# Motor.net
KiCad netlist of a schematic drawn in Altium Designer
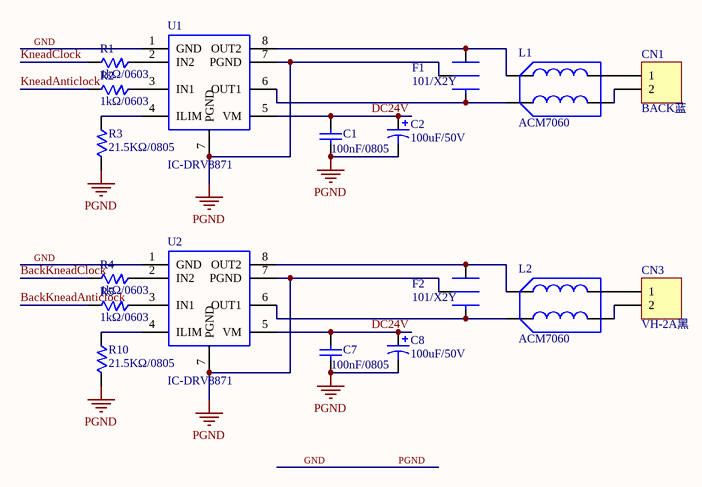
[diagram p0: Motor.SchDoc]

(export (version "E")
  (design (tool "Eeschema 10.0.6"))
  (components
    (comp (ref "C1") (value "100nF/0805") (footprint "0805C") (libsource (lib "荣泰料号库") (part "C0805/104M")))
    (comp (ref "C2")
      (value "100uF/50V")
      (footprint "RB.15/.35")
      (libsource (lib "荣泰料号库") (part "CD/100uF/50V"))
    )
    (comp (ref "C7") (value "100nF/0805") (footprint "0805C") (libsource (lib "荣泰料号库") (part "C0805/104M")))
    (comp (ref "C8")
      (value "100uF/50V")
      (footprint "RB.15/.35")
      (libsource (lib "荣泰料号库") (part "CD/100uF/50V"))
    )
    (comp (ref "CN1")
      (value "BACK蓝")
      (footprint "CON-VH-2P")
      (libsource (lib "荣泰料号库") (part "CON-VH-2A(蓝色)"))
    )
    (comp (ref "CN3")
      (value "VH-2A黑")
      (footprint "CON-VH-2P")
      (libsource (lib "荣泰料号库") (part "CON-VH-2A(黑色)"))
    )
    (comp (ref "F1") (value "101/X2Y") (footprint "X2Y") (libsource (lib "荣泰料号库") (part "CX2Y/101")))
    (comp (ref "F2") (value "101/X2Y") (footprint "X2Y") (libsource (lib "荣泰料号库") (part "CX2Y/101")))
    (comp (ref "L1") (value "ACM7060") (footprint "TLDCM7161") (libsource (lib "荣泰料号库") (part "L/ACM7060")))
    (comp (ref "L2") (value "ACM7060") (footprint "TLDCM7161") (libsource (lib "荣泰料号库") (part "L/ACM7060")))
    (comp (ref "R1") (value "1kΩ/0603") (footprint "0603") (libsource (lib "荣泰料号库") (part "R0603/1kΩ")))
    (comp (ref "R2") (value "1kΩ/0603") (footprint "0603") (libsource (lib "荣泰料号库") (part "R0603/1kΩ")))
    (comp (ref "R3")
      (value "21.5KΩ/0805")
      (footprint "0603")
      (libsource (lib "荣泰料号库") (part "R0603/21.5KΩ 1%"))
    )
    (comp (ref "R4") (value "1kΩ/0603") (footprint "0603") (libsource (lib "荣泰料号库") (part "R0603/1kΩ")))
    (comp (ref "R5") (value "1kΩ/0603") (footprint "0603") (libsource (lib "荣泰料号库") (part "R0603/1kΩ")))
    (comp (ref "R10")
      (value "21.5KΩ/0805")
      (footprint "0603")
      (libsource (lib "荣泰料号库") (part "R0603/21.5KΩ 1%"))
    )
    (comp (ref "U1") (value "IC-DRV8871") (footprint "DRV8871") (libsource (lib "荣泰料号库") (part "IC-DRV8871")))
    (comp (ref "U2") (value "IC-DRV8871") (footprint "DRV8871") (libsource (lib "荣泰料号库") (part "IC-DRV8871")))
  )
  (nets
    (net (code "1") (name "/BackKneadAnticlock") (class "Default")
      (node (ref "R5") (pin "1") (pinfunction "1_1") (pintype "passive"))
    )
    (net (code "2") (name "/BackKneadClock") (class "Default")
      (node (ref "R4") (pin "1") (pinfunction "1_1") (pintype "passive"))
    )
    (net (code "3") (name "/DC24V") (class "Default")
      (node (ref "C1") (pin "2") (pinfunction "2_2") (pintype "passive"))
      (node (ref "C2") (pin "1") (pinfunction "1_1") (pintype "passive"))
      (node (ref "C7") (pin "2") (pinfunction "2_2") (pintype "passive"))
      (node (ref "C8") (pin "1") (pinfunction "1_1") (pintype "passive"))
      (node (ref "U1") (pin "5") (pinfunction "VM_5") (pintype "passive"))
      (node (ref "U2") (pin "5") (pinfunction "VM_5") (pintype "passive"))
    )
    (net (code "4") (name "/KneadAnticlock") (class "Default")
      (node (ref "R2") (pin "1") (pinfunction "1_1") (pintype "passive"))
    )
    (net (code "5") (name "/KneadClock") (class "Default")
      (node (ref "R1") (pin "1") (pinfunction "1_1") (pintype "passive"))
    )
    (net (code "6") (name "Net-(CN1-Pad1)") (class "Default")
      (node (ref "CN1") (pin "1") (pinfunction "1_1") (pintype "passive"))
      (node (ref "L1") (pin "3") (pinfunction "3_3") (pintype "passive"))
    )
    (net (code "7") (name "Net-(CN1-Pad2)") (class "Default")
      (node (ref "CN1") (pin "2") (pinfunction "2_2") (pintype "passive"))
      (node (ref "L1") (pin "4") (pinfunction "4_4") (pintype "passive"))
    )
    (net (code "8") (name "Net-(CN3-Pad1)") (class "Default")
      (node (ref "CN3") (pin "1") (pinfunction "1_1") (pintype "passive"))
      (node (ref "L2") (pin "3") (pinfunction "3_3") (pintype "passive"))
    )
    (net (code "9") (name "Net-(CN3-Pad2)") (class "Default")
      (node (ref "CN3") (pin "2") (pinfunction "2_2") (pintype "passive"))
      (node (ref "L2") (pin "4") (pinfunction "4_4") (pintype "passive"))
    )
    (net (code "10") (name "Net-(U1-ILIM)") (class "Default")
      (node (ref "R3") (pin "2") (pinfunction "2_2") (pintype "passive"))
      (node (ref "U1") (pin "4") (pinfunction "ILIM_4") (pintype "passive"))
    )
    (net (code "11") (name "Net-(U1-IN1)") (class "Default")
      (node (ref "R2") (pin "2") (pinfunction "2_2") (pintype "passive"))
      (node (ref "U1") (pin "3") (pinfunction "IN1_3") (pintype "passive"))
    )
    (net (code "12") (name "Net-(U1-IN2)") (class "Default")
      (node (ref "R1") (pin "2") (pinfunction "2_2") (pintype "passive"))
      (node (ref "U1") (pin "2") (pinfunction "IN2_2") (pintype "passive"))
    )
    (net (code "13") (name "Net-(U1-OUT1)") (class "Default")
      (node (ref "F1") (pin "2") (pinfunction "2_2") (pintype "passive"))
      (node (ref "L1") (pin "1") (pinfunction "1_1") (pintype "passive"))
      (node (ref "U1") (pin "6") (pinfunction "OUT1_6") (pintype "passive"))
    )
    (net (code "14") (name "Net-(U1-OUT2)") (class "Default")
      (node (ref "F1") (pin "1") (pinfunction "1_1") (pintype "passive"))
      (node (ref "L1") (pin "2") (pinfunction "2_2") (pintype "passive"))
      (node (ref "U1") (pin "8") (pinfunction "OUT2_8") (pintype "passive"))
    )
    (net (code "15") (name "Net-(U2-ILIM)") (class "Default")
      (node (ref "R10") (pin "2") (pinfunction "2_2") (pintype "passive"))
      (node (ref "U2") (pin "4") (pinfunction "ILIM_4") (pintype "passive"))
    )
    (net (code "16") (name "Net-(U2-IN1)") (class "Default")
      (node (ref "R5") (pin "2") (pinfunction "2_2") (pintype "passive"))
      (node (ref "U2") (pin "3") (pinfunction "IN1_3") (pintype "passive"))
    )
    (net (code "17") (name "Net-(U2-IN2)") (class "Default")
      (node (ref "R4") (pin "2") (pinfunction "2_2") (pintype "passive"))
      (node (ref "U2") (pin "2") (pinfunction "IN2_2") (pintype "passive"))
    )
    (net (code "18") (name "Net-(U2-OUT1)") (class "Default")
      (node (ref "F2") (pin "2") (pinfunction "2_2") (pintype "passive"))
      (node (ref "L2") (pin "1") (pinfunction "1_1") (pintype "passive"))
      (node (ref "U2") (pin "6") (pinfunction "OUT1_6") (pintype "passive"))
    )
    (net (code "19") (name "Net-(U2-OUT2)") (class "Default")
      (node (ref "F2") (pin "1") (pinfunction "1_1") (pintype "passive"))
      (node (ref "L2") (pin "2") (pinfunction "2_2") (pintype "passive"))
      (node (ref "U2") (pin "8") (pinfunction "OUT2_8") (pintype "passive"))
    )
    (net (code "20") (name "PGND") (class "Default")
      (node (ref "C1") (pin "1") (pinfunction "1_1") (pintype "passive"))
      (node (ref "C2") (pin "2") (pinfunction "2_2") (pintype "passive"))
      (node (ref "C7") (pin "1") (pinfunction "1_1") (pintype "passive"))
      (node (ref "C8") (pin "2") (pinfunction "2_2") (pintype "passive"))
      (node (ref "F1") (pin "3") (pinfunction "3_3") (pintype "passive"))
      (node (ref "F2") (pin "3") (pinfunction "3_3") (pintype "passive"))
      (node (ref "R10") (pin "1") (pinfunction "1_1") (pintype "passive"))
      (node (ref "R3") (pin "1") (pinfunction "1_1") (pintype "passive"))
      (node (ref "U1") (pin "1") (pinfunction "GND_1") (pintype "passive"))
      (node (ref "U1") (pin "7") (pinfunction "PGND_7") (pintype "passive"))
      (node (ref "U2") (pin "1") (pinfunction "GND_1") (pintype "passive"))
      (node (ref "U2") (pin "7") (pinfunction "PGND_7") (pintype "passive"))
    )
  )
)
